# Digital_-_BlackChat.net
KiCad netlist of a schematic drawn in Altium Designer
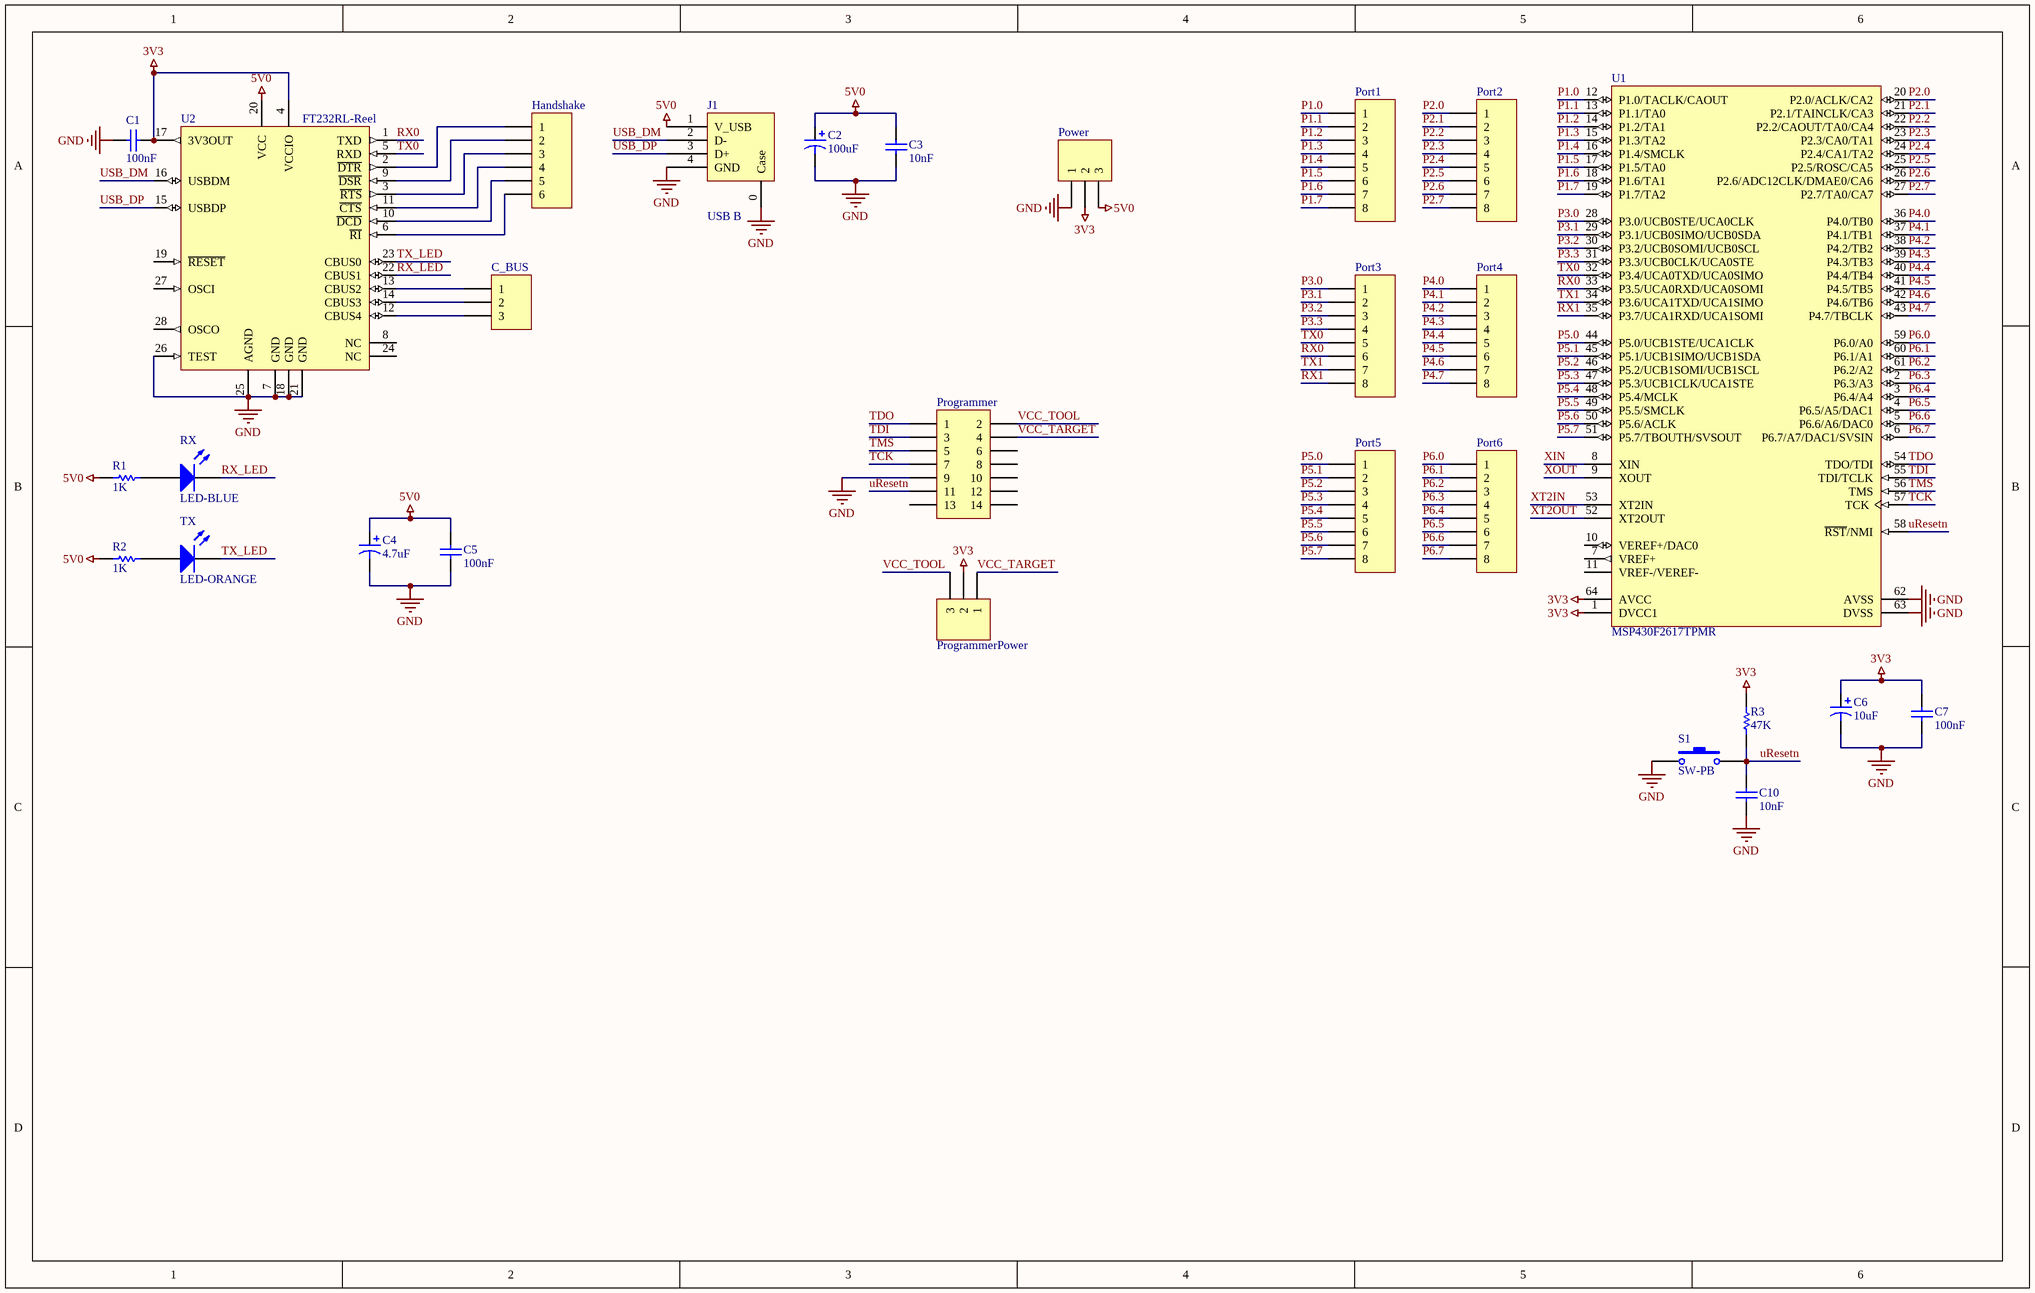
[diagram p0: Digital - BlackChat.SchDoc]

(export (version "E")
  (design (tool "Eeschema 10.0.6"))
  (components
    (comp (ref "C1")
      (value "100nF")
      (footprint "CAP-0805")
      (description "Capacitor")
      (fields (field (name "Comment") "Cap") (field (name "PUBLISHER") "Altium Limited"))
      (libsource (lib "Miscellaneous Devices") (part "Cap"))
    )
    (comp (ref "C2")
      (value "100uF")
      (footprint "CAP-0805")
      (description "Polarized Capacitor (Surface Mount)")
      (fields (field (name "Comment") "Cap Pol3") (field (name "PUBLISHER") "Altium Limited"))
      (libsource (lib "Miscellaneous Devices") (part "Cap Pol3"))
    )
    (comp (ref "C3")
      (value "10nF")
      (footprint "CAP-0805")
      (description "Capacitor")
      (fields (field (name "Comment") "Cap") (field (name "PUBLISHER") "Altium Limited"))
      (libsource (lib "Miscellaneous Devices") (part "Cap"))
    )
    (comp (ref "C4")
      (value "4.7uF")
      (footprint "CAP-0805")
      (description "Polarized Capacitor (Surface Mount)")
      (fields (field (name "Comment") "Cap Pol3") (field (name "PUBLISHER") "Altium Limited"))
      (libsource (lib "Miscellaneous Devices") (part "Cap Pol3"))
    )
    (comp (ref "C5")
      (value "100nF")
      (footprint "CAP-0805")
      (description "Capacitor")
      (fields (field (name "Comment") "Cap") (field (name "PUBLISHER") "Altium Limited"))
      (libsource (lib "Miscellaneous Devices") (part "Cap"))
    )
    (comp (ref "C6")
      (value "10uF")
      (footprint "CAP-0805")
      (description "Polarized Capacitor (Surface Mount)")
      (fields (field (name "Comment") "Cap Pol3") (field (name "PUBLISHER") "Altium Limited"))
      (libsource (lib "Miscellaneous Devices") (part "Cap Pol3"))
    )
    (comp (ref "C7")
      (value "100nF")
      (footprint "CAP-0805")
      (description "Capacitor")
      (fields (field (name "Comment") "Cap") (field (name "PUBLISHER") "Altium Limited"))
      (libsource (lib "Miscellaneous Devices") (part "Cap"))
    )
    (comp (ref "C10")
      (value "10nF")
      (footprint "CAP-0805")
      (description "Capacitor")
      (fields (field (name "Comment") "Cap") (field (name "PUBLISHER") "Altium Limited"))
      (libsource (lib "Miscellaneous Devices") (part "Cap"))
    )
    (comp (ref "C_BUS")
      (value "Header 3")
      (footprint "HDR1X3")
      (description "Header, 3-Pin")
      (fields (field (name "PUBLISHER") "Altium Limited"))
      (libsource (lib "") (part "Header 3_1"))
    )
    (comp (ref "Handshake")
      (value "Header 6")
      (footprint "HDR1X6")
      (description "Header, 6-Pin")
      (fields (field (name "PUBLISHER") "Altium Limited"))
      (libsource (lib "Miscellaneous Connectors") (part "Header 6"))
    )
    (comp (ref "J1")
      (value "USB B")
      (footprint "USB-B")
      (description "On Shore Technology USB-B1HSB6")
      (libsource (lib "BlackChat Library") (part "USB B"))
    )
    (comp (ref "Port1")
      (value "~")
      (footprint "HDR1X8")
      (description "Header, 8-Pin")
      (fields (field (name "PUBLISHER") "Altium Limited"))
      (libsource (lib "Miscellaneous Connectors") (part "Header 8"))
    )
    (comp (ref "Port2")
      (value "~")
      (footprint "HDR1X8")
      (description "Header, 8-Pin")
      (fields (field (name "PUBLISHER") "Altium Limited"))
      (libsource (lib "Miscellaneous Connectors") (part "Header 8"))
    )
    (comp (ref "Port3")
      (value "Header 8")
      (footprint "HDR1X8")
      (description "Header, 8-Pin")
      (fields (field (name "PUBLISHER") "Altium Limited"))
      (libsource (lib "Miscellaneous Connectors") (part "Header 8"))
    )
    (comp (ref "Port4")
      (value "Header 8")
      (footprint "HDR1X8")
      (description "Header, 8-Pin")
      (fields (field (name "PUBLISHER") "Altium Limited"))
      (libsource (lib "Miscellaneous Connectors") (part "Header 8"))
    )
    (comp (ref "Port5")
      (value "Header 8")
      (footprint "HDR1X8")
      (description "Header, 8-Pin")
      (fields (field (name "PUBLISHER") "Altium Limited"))
      (libsource (lib "Miscellaneous Connectors") (part "Header 8"))
    )
    (comp (ref "Port6")
      (value "Header 8")
      (footprint "HDR1X8")
      (description "Header, 8-Pin")
      (fields (field (name "PUBLISHER") "Altium Limited"))
      (libsource (lib "Miscellaneous Connectors") (part "Header 8"))
    )
    (comp (ref "Power")
      (value "Header 3")
      (footprint "HDR1X3")
      (description "Header, 3-Pin")
      (fields (field (name "PUBLISHER") "Altium Limited"))
      (libsource (lib "") (part "Header 3_2"))
    )
    (comp (ref "Programmer")
      (value "Header 7X2")
      (footprint "HDR2X7")
      (description "Header, 7-Pin, Dual row")
      (fields (field (name "PUBLISHER") "Altium Limited"))
      (libsource (lib "Miscellaneous Connectors") (part "Header 7X2"))
    )
    (comp (ref "ProgrammerPower")
      (value "Header 3")
      (footprint "HDR1X3")
      (description "Header, 3-Pin")
      (fields (field (name "PUBLISHER") "Altium Limited"))
      (libsource (lib "Miscellaneous Connectors") (part "Header 3"))
    )
    (comp (ref "R1")
      (value "1K")
      (footprint "RES-0805")
      (description "Resistor")
      (fields (field (name "Comment") "Res1") (field (name "PUBLISHER") "Altium Limited"))
      (libsource (lib "Miscellaneous Devices") (part "Res1"))
    )
    (comp (ref "R2")
      (value "1K")
      (footprint "RES-0805")
      (description "Resistor")
      (fields (field (name "Comment") "Res1") (field (name "PUBLISHER") "Altium Limited"))
      (libsource (lib "Miscellaneous Devices") (part "Res1"))
    )
    (comp (ref "R3")
      (value "47K")
      (footprint "RES-0805")
      (description "Resistor")
      (fields (field (name "Comment") "Res1") (field (name "PUBLISHER") "Altium Limited"))
      (libsource (lib "Miscellaneous Devices") (part "Res1"))
    )
    (comp (ref "RX")
      (value "LED-BLUE")
      (footprint "LED-0805")
      (description "Light Emitting Diode")
      (libsource (lib "BlackChat Library") (part "LED-GENERIC"))
    )
    (comp (ref "S1")
      (value "SW-PB")
      (footprint "SW PB")
      (description "DIGIKEY SW400-ND")
      (fields (field (name "PUBLISHER") "Altium Limited"))
      (libsource (lib "ECE Lib") (part "SW-PB"))
    )
    (comp (ref "TX")
      (value "LED-ORANGE")
      (footprint "LED-0805")
      (description "Light Emitting Diode")
      (libsource (lib "BlackChat Library") (part "LED-GENERIC"))
    )
    (comp (ref "U1")
      (value "MSP430F2617TPMR")
      (footprint "TI-PM64_N")
      (fields (field (name "MANUFACTURER") "Texas Instruments"))
      (libsource (lib "TI Microcontroller MSP430 16-bit Ultra-Low Power") (part "MSP430F2617TPMR"))
    )
    (comp (ref "U2")
      (value "FT232RL-Reel")
      (footprint "SSOP-28_N")
      (description "USB UART Asynchronous Serial Data Transfer Chip, SSOP-28, Tape and Reel")
      (fields (field (name "PUBLISHER") "Altium Limited"))
      (libsource (lib "BlackChat Library") (part "FT232RL-Reel"))
    )
  )
  (nets
    (net (code "1") (name "/P1.0") (class "Default")
      (node (ref "Port1") (pin "1") (pinfunction "1_1") (pintype "passive"))
      (node (ref "U1") (pin "12") (pinfunction "P1.0/TACLK/CAOUT_12") (pintype "bidirectional"))
    )
    (net (code "2") (name "/P1.1") (class "Default")
      (node (ref "Port1") (pin "2") (pinfunction "2_2") (pintype "passive"))
      (node (ref "U1") (pin "13") (pinfunction "P1.1/TA0_13") (pintype "bidirectional"))
    )
    (net (code "3") (name "/P1.2") (class "Default")
      (node (ref "Port1") (pin "3") (pinfunction "3_3") (pintype "passive"))
      (node (ref "U1") (pin "14") (pinfunction "P1.2/TA1_14") (pintype "bidirectional"))
    )
    (net (code "4") (name "/P1.3") (class "Default")
      (node (ref "Port1") (pin "4") (pinfunction "4_4") (pintype "passive"))
      (node (ref "U1") (pin "15") (pinfunction "P1.3/TA2_15") (pintype "bidirectional"))
    )
    (net (code "5") (name "/P1.4") (class "Default")
      (node (ref "Port1") (pin "5") (pinfunction "5_5") (pintype "passive"))
      (node (ref "U1") (pin "16") (pinfunction "P1.4/SMCLK_16") (pintype "bidirectional"))
    )
    (net (code "6") (name "/P1.5") (class "Default")
      (node (ref "Port1") (pin "6") (pinfunction "6_6") (pintype "passive"))
      (node (ref "U1") (pin "17") (pinfunction "P1.5/TA0_17") (pintype "bidirectional"))
    )
    (net (code "7") (name "/P1.6") (class "Default")
      (node (ref "Port1") (pin "7") (pinfunction "7_7") (pintype "passive"))
      (node (ref "U1") (pin "18") (pinfunction "P1.6/TA1_18") (pintype "bidirectional"))
    )
    (net (code "8") (name "/P1.7") (class "Default")
      (node (ref "Port1") (pin "8") (pinfunction "8_8") (pintype "passive"))
      (node (ref "U1") (pin "19") (pinfunction "P1.7/TA2_19") (pintype "bidirectional"))
    )
    (net (code "9") (name "/P2.0") (class "Default")
      (node (ref "Port2") (pin "1") (pinfunction "1_1") (pintype "passive"))
      (node (ref "U1") (pin "20") (pinfunction "P2.0/ACLK/CA2_20") (pintype "bidirectional"))
    )
    (net (code "10") (name "/P2.1") (class "Default")
      (node (ref "Port2") (pin "2") (pinfunction "2_2") (pintype "passive"))
      (node (ref "U1") (pin "21") (pinfunction "P2.1/TAINCLK/CA3_21") (pintype "bidirectional"))
    )
    (net (code "11") (name "/P2.2") (class "Default")
      (node (ref "Port2") (pin "3") (pinfunction "3_3") (pintype "passive"))
      (node (ref "U1") (pin "22") (pinfunction "P2.2/CAOUT/TA0/CA4_22") (pintype "bidirectional"))
    )
    (net (code "12") (name "/P2.3") (class "Default")
      (node (ref "Port2") (pin "4") (pinfunction "4_4") (pintype "passive"))
      (node (ref "U1") (pin "23") (pinfunction "P2.3/CA0/TA1_23") (pintype "bidirectional"))
    )
    (net (code "13") (name "/P2.4") (class "Default")
      (node (ref "Port2") (pin "5") (pinfunction "5_5") (pintype "passive"))
      (node (ref "U1") (pin "24") (pinfunction "P2.4/CA1/TA2_24") (pintype "bidirectional"))
    )
    (net (code "14") (name "/P2.5") (class "Default")
      (node (ref "Port2") (pin "6") (pinfunction "6_6") (pintype "passive"))
      (node (ref "U1") (pin "25") (pinfunction "P2.5/ROSC/CA5_25") (pintype "bidirectional"))
    )
    (net (code "15") (name "/P2.6") (class "Default")
      (node (ref "Port2") (pin "7") (pinfunction "7_7") (pintype "passive"))
      (node (ref "U1") (pin "26") (pinfunction "P2.6/ADC12CLK/DMAE0/CA6_26") (pintype "bidirectional"))
    )
    (net (code "16") (name "/P2.7") (class "Default")
      (node (ref "Port2") (pin "8") (pinfunction "8_8") (pintype "passive"))
      (node (ref "U1") (pin "27") (pinfunction "P2.7/TA0/CA7_27") (pintype "bidirectional"))
    )
    (net (code "17") (name "/P3.0") (class "Default")
      (node (ref "Port3") (pin "1") (pinfunction "1_1") (pintype "passive"))
      (node (ref "U1") (pin "28") (pinfunction "P3.0/UCB0STE/UCA0CLK_28") (pintype "bidirectional"))
    )
    (net (code "18") (name "/P3.1") (class "Default")
      (node (ref "Port3") (pin "2") (pinfunction "2_2") (pintype "passive"))
      (node (ref "U1") (pin "29") (pinfunction "P3.1/UCB0SIMO/UCB0SDA_29") (pintype "bidirectional"))
    )
    (net (code "19") (name "/P3.2") (class "Default")
      (node (ref "Port3") (pin "3") (pinfunction "3_3") (pintype "passive"))
      (node (ref "U1") (pin "30") (pinfunction "P3.2/UCB0SOMI/UCB0SCL_30") (pintype "bidirectional"))
    )
    (net (code "20") (name "/P3.3") (class "Default")
      (node (ref "Port3") (pin "4") (pinfunction "4_4") (pintype "passive"))
      (node (ref "U1") (pin "31") (pinfunction "P3.3/UCB0CLK/UCA0STE_31") (pintype "bidirectional"))
    )
    (net (code "21") (name "/P4.0") (class "Default")
      (node (ref "Port4") (pin "1") (pinfunction "1_1") (pintype "passive"))
      (node (ref "U1") (pin "36") (pinfunction "P4.0/TB0_36") (pintype "bidirectional"))
    )
    (net (code "22") (name "/P4.1") (class "Default")
      (node (ref "Port4") (pin "2") (pinfunction "2_2") (pintype "passive"))
      (node (ref "U1") (pin "37") (pinfunction "P4.1/TB1_37") (pintype "bidirectional"))
    )
    (net (code "23") (name "/P4.2") (class "Default")
      (node (ref "Port4") (pin "3") (pinfunction "3_3") (pintype "passive"))
      (node (ref "U1") (pin "38") (pinfunction "P4.2/TB2_38") (pintype "bidirectional"))
    )
    (net (code "24") (name "/P4.3") (class "Default")
      (node (ref "Port4") (pin "4") (pinfunction "4_4") (pintype "passive"))
      (node (ref "U1") (pin "39") (pinfunction "P4.3/TB3_39") (pintype "bidirectional"))
    )
    (net (code "25") (name "/P4.4") (class "Default")
      (node (ref "Port4") (pin "5") (pinfunction "5_5") (pintype "passive"))
      (node (ref "U1") (pin "40") (pinfunction "P4.4/TB4_40") (pintype "bidirectional"))
    )
    (net (code "26") (name "/P4.5") (class "Default")
      (node (ref "Port4") (pin "6") (pinfunction "6_6") (pintype "passive"))
      (node (ref "U1") (pin "41") (pinfunction "P4.5/TB5_41") (pintype "bidirectional"))
    )
    (net (code "27") (name "/P4.6") (class "Default")
      (node (ref "Port4") (pin "7") (pinfunction "7_7") (pintype "passive"))
      (node (ref "U1") (pin "42") (pinfunction "P4.6/TB6_42") (pintype "bidirectional"))
    )
    (net (code "28") (name "/P4.7") (class "Default")
      (node (ref "Port4") (pin "8") (pinfunction "8_8") (pintype "passive"))
      (node (ref "U1") (pin "43") (pinfunction "P4.7/TBCLK_43") (pintype "bidirectional"))
    )
    (net (code "29") (name "/P5.0") (class "Default")
      (node (ref "Port5") (pin "1") (pinfunction "1_1") (pintype "passive"))
      (node (ref "U1") (pin "44") (pinfunction "P5.0/UCB1STE/UCA1CLK_44") (pintype "bidirectional"))
    )
    (net (code "30") (name "/P5.1") (class "Default")
      (node (ref "Port5") (pin "2") (pinfunction "2_2") (pintype "passive"))
      (node (ref "U1") (pin "45") (pinfunction "P5.1/UCB1SIMO/UCB1SDA_45") (pintype "bidirectional"))
    )
    (net (code "31") (name "/P5.2") (class "Default")
      (node (ref "Port5") (pin "3") (pinfunction "3_3") (pintype "passive"))
      (node (ref "U1") (pin "46") (pinfunction "P5.2/UCB1SOMI/UCB1SCL_46") (pintype "bidirectional"))
    )
    (net (code "32") (name "/P5.3") (class "Default")
      (node (ref "Port5") (pin "4") (pinfunction "4_4") (pintype "passive"))
      (node (ref "U1") (pin "47") (pinfunction "P5.3/UCB1CLK/UCA1STE_47") (pintype "bidirectional"))
    )
    (net (code "33") (name "/P5.4") (class "Default")
      (node (ref "Port5") (pin "5") (pinfunction "5_5") (pintype "passive"))
      (node (ref "U1") (pin "48") (pinfunction "P5.4/MCLK_48") (pintype "bidirectional"))
    )
    (net (code "34") (name "/P5.5") (class "Default")
      (node (ref "Port5") (pin "6") (pinfunction "6_6") (pintype "passive"))
      (node (ref "U1") (pin "49") (pinfunction "P5.5/SMCLK_49") (pintype "bidirectional"))
    )
    (net (code "35") (name "/P5.6") (class "Default")
      (node (ref "Port5") (pin "7") (pinfunction "7_7") (pintype "passive"))
      (node (ref "U1") (pin "50") (pinfunction "P5.6/ACLK_50") (pintype "bidirectional"))
    )
    (net (code "36") (name "/P5.7") (class "Default")
      (node (ref "Port5") (pin "8") (pinfunction "8_8") (pintype "passive"))
      (node (ref "U1") (pin "51") (pinfunction "P5.7/TBOUTH/SVSOUT_51") (pintype "bidirectional"))
    )
    (net (code "37") (name "/P6.0") (class "Default")
      (node (ref "Port6") (pin "1") (pinfunction "1_1") (pintype "passive"))
      (node (ref "U1") (pin "59") (pinfunction "P6.0/A0_59") (pintype "bidirectional"))
    )
    (net (code "38") (name "/P6.1") (class "Default")
      (node (ref "Port6") (pin "2") (pinfunction "2_2") (pintype "passive"))
      (node (ref "U1") (pin "60") (pinfunction "P6.1/A1_60") (pintype "bidirectional"))
    )
    (net (code "39") (name "/P6.2") (class "Default")
      (node (ref "Port6") (pin "3") (pinfunction "3_3") (pintype "passive"))
      (node (ref "U1") (pin "61") (pinfunction "P6.2/A2_61") (pintype "bidirectional"))
    )
    (net (code "40") (name "/P6.3") (class "Default")
      (node (ref "Port6") (pin "4") (pinfunction "4_4") (pintype "passive"))
      (node (ref "U1") (pin "2") (pinfunction "P6.3/A3_2") (pintype "bidirectional"))
    )
    (net (code "41") (name "/P6.4") (class "Default")
      (node (ref "Port6") (pin "5") (pinfunction "5_5") (pintype "passive"))
      (node (ref "U1") (pin "3") (pinfunction "P6.4/A4_3") (pintype "bidirectional"))
    )
    (net (code "42") (name "/P6.5") (class "Default")
      (node (ref "Port6") (pin "6") (pinfunction "6_6") (pintype "passive"))
      (node (ref "U1") (pin "4") (pinfunction "P6.5/A5/DAC1_4") (pintype "bidirectional"))
    )
    (net (code "43") (name "/P6.6") (class "Default")
      (node (ref "Port6") (pin "7") (pinfunction "7_7") (pintype "passive"))
      (node (ref "U1") (pin "5") (pinfunction "P6.6/A6/DAC0_5") (pintype "bidirectional"))
    )
    (net (code "44") (name "/P6.7") (class "Default")
      (node (ref "Port6") (pin "8") (pinfunction "8_8") (pintype "passive"))
      (node (ref "U1") (pin "6") (pinfunction "P6.7/A7/DAC1/SVSIN_6") (pintype "bidirectional"))
    )
    (net (code "45") (name "/RX0") (class "Default")
      (node (ref "Port3") (pin "6") (pinfunction "6_6") (pintype "passive"))
      (node (ref "U1") (pin "33") (pinfunction "P3.5/UCA0RXD/UCA0SOMI_33") (pintype "bidirectional"))
      (node (ref "U2") (pin "1") (pinfunction "TXD_1") (pintype "output"))
    )
    (net (code "46") (name "/RX1") (class "Default")
      (node (ref "Port3") (pin "8") (pinfunction "8_8") (pintype "passive"))
      (node (ref "U1") (pin "35") (pinfunction "P3.7/UCA1RXD/UCA1SOMI_35") (pintype "bidirectional"))
    )
    (net (code "47") (name "/RX_LED") (class "Default")
      (node (ref "RX") (pin "2") (pinfunction "K_2") (pintype "passive"))
      (node (ref "U2") (pin "22") (pinfunction "CBUS1_22") (pintype "bidirectional"))
    )
    (net (code "48") (name "/TCK") (class "Default")
      (node (ref "Programmer") (pin "7") (pinfunction "7_7") (pintype "passive"))
      (node (ref "U1") (pin "57") (pinfunction "TCK_57") (pintype "input"))
    )
    (net (code "49") (name "/TDI") (class "Default")
      (node (ref "Programmer") (pin "3") (pinfunction "3_3") (pintype "passive"))
      (node (ref "U1") (pin "55") (pinfunction "TDI/TCLK_55") (pintype "input"))
    )
    (net (code "50") (name "/TDO") (class "Default")
      (node (ref "Programmer") (pin "1") (pinfunction "1_1") (pintype "passive"))
      (node (ref "U1") (pin "54") (pinfunction "TDO/TDI_54") (pintype "bidirectional"))
    )
    (net (code "51") (name "/TMS") (class "Default")
      (node (ref "Programmer") (pin "5") (pinfunction "5_5") (pintype "passive"))
      (node (ref "U1") (pin "56") (pinfunction "TMS_56") (pintype "input"))
    )
    (net (code "52") (name "/TX0") (class "Default")
      (node (ref "Port3") (pin "5") (pinfunction "5_5") (pintype "passive"))
      (node (ref "U1") (pin "32") (pinfunction "P3.4/UCA0TXD/UCA0SIMO_32") (pintype "bidirectional"))
      (node (ref "U2") (pin "5") (pinfunction "RXD_5") (pintype "input"))
    )
    (net (code "53") (name "/TX1") (class "Default")
      (node (ref "Port3") (pin "7") (pinfunction "7_7") (pintype "passive"))
      (node (ref "U1") (pin "34") (pinfunction "P3.6/UCA1TXD/UCA1SIMO_34") (pintype "bidirectional"))
    )
    (net (code "54") (name "/TX_LED") (class "Default")
      (node (ref "TX") (pin "2") (pinfunction "K_2") (pintype "passive"))
      (node (ref "U2") (pin "23") (pinfunction "CBUS0_23") (pintype "bidirectional"))
    )
    (net (code "55") (name "/USB_DM") (class "Default")
      (node (ref "J1") (pin "2") (pinfunction "D-_2") (pintype "passive"))
      (node (ref "U2") (pin "16") (pinfunction "USBDM_16") (pintype "bidirectional"))
    )
    (net (code "56") (name "/USB_DP") (class "Default")
      (node (ref "J1") (pin "3") (pinfunction "D+_3") (pintype "passive"))
      (node (ref "U2") (pin "15") (pinfunction "USBDP_15") (pintype "bidirectional"))
    )
    (net (code "57") (name "/VCC_TARGET") (class "Default")
      (node (ref "Programmer") (pin "4") (pinfunction "4_4") (pintype "passive"))
      (node (ref "ProgrammerPower") (pin "1") (pinfunction "1_1") (pintype "passive"))
    )
    (net (code "58") (name "/VCC_TOOL") (class "Default")
      (node (ref "Programmer") (pin "2") (pinfunction "2_2") (pintype "passive"))
      (node (ref "ProgrammerPower") (pin "3") (pinfunction "3_3") (pintype "passive"))
    )
    (net (code "59") (name "/XIN") (class "Default")
      (node (ref "U1") (pin "8") (pinfunction "XIN_8") (pintype "passive"))
    )
    (net (code "60") (name "/XOUT") (class "Default")
      (node (ref "U1") (pin "9") (pinfunction "XOUT_9") (pintype "passive"))
    )
    (net (code "61") (name "/XT2IN") (class "Default")
      (node (ref "U1") (pin "53") (pinfunction "XT2IN_53") (pintype "passive"))
    )
    (net (code "62") (name "/XT2OUT") (class "Default")
      (node (ref "U1") (pin "52") (pinfunction "XT2OUT_52") (pintype "passive"))
    )
    (net (code "63") (name "/uResetn") (class "Default")
      (node (ref "C10") (pin "2") (pinfunction "2_2") (pintype "passive"))
      (node (ref "Programmer") (pin "11") (pinfunction "11_11") (pintype "passive"))
      (node (ref "R3") (pin "1") (pinfunction "1_1") (pintype "passive"))
      (node (ref "S1") (pin "2") (pinfunction "2_2") (pintype "passive"))
      (node (ref "U1") (pin "58") (pinfunction "~{RST}/NMI_58") (pintype "input"))
    )
    (net (code "64") (name "3V3") (class "Default")
      (node (ref "C1") (pin "1") (pinfunction "1_1") (pintype "passive"))
      (node (ref "C6") (pin "1") (pinfunction "1_1") (pintype "passive"))
      (node (ref "C7") (pin "2") (pinfunction "2_2") (pintype "passive"))
      (node (ref "Power") (pin "2") (pinfunction "2_2") (pintype "passive"))
      (node (ref "ProgrammerPower") (pin "2") (pinfunction "2_2") (pintype "passive"))
      (node (ref "R3") (pin "2") (pinfunction "2_2") (pintype "passive"))
      (node (ref "U1") (pin "1") (pinfunction "DVCC1_1") (pintype "power_in"))
      (node (ref "U1") (pin "64") (pinfunction "AVCC_64") (pintype "power_in"))
      (node (ref "U2") (pin "17") (pinfunction "3V3OUT_17") (pintype "output"))
      (node (ref "U2") (pin "4") (pinfunction "VCCIO_4") (pintype "power_in"))
    )
    (net (code "65") (name "5V0") (class "Default")
      (node (ref "C2") (pin "1") (pinfunction "1_1") (pintype "passive"))
      (node (ref "C3") (pin "2") (pinfunction "2_2") (pintype "passive"))
      (node (ref "C4") (pin "1") (pinfunction "1_1") (pintype "passive"))
      (node (ref "C5") (pin "2") (pinfunction "2_2") (pintype "passive"))
      (node (ref "J1") (pin "1") (pinfunction "V_USB_1") (pintype "passive"))
      (node (ref "Power") (pin "3") (pinfunction "3_3") (pintype "passive"))
      (node (ref "R1") (pin "2") (pinfunction "2_2") (pintype "passive"))
      (node (ref "R2") (pin "2") (pinfunction "2_2") (pintype "passive"))
      (node (ref "U2") (pin "20") (pinfunction "VCC_20") (pintype "power_in"))
    )
    (net (code "66") (name "GND") (class "Default")
      (node (ref "C1") (pin "2") (pinfunction "2_2") (pintype "passive"))
      (node (ref "C10") (pin "1") (pinfunction "1_1") (pintype "passive"))
      (node (ref "C2") (pin "2") (pinfunction "2_2") (pintype "passive"))
      (node (ref "C3") (pin "1") (pinfunction "1_1") (pintype "passive"))
      (node (ref "C4") (pin "2") (pinfunction "2_2") (pintype "passive"))
      (node (ref "C5") (pin "1") (pinfunction "1_1") (pintype "passive"))
      (node (ref "C6") (pin "2") (pinfunction "2_2") (pintype "passive"))
      (node (ref "C7") (pin "1") (pinfunction "1_1") (pintype "passive"))
      (node (ref "J1") (pin "0") (pinfunction "Case_0") (pintype "passive"))
      (node (ref "J1") (pin "4") (pinfunction "GND_4") (pintype "passive"))
      (node (ref "Power") (pin "1") (pinfunction "1_1") (pintype "passive"))
      (node (ref "Programmer") (pin "9") (pinfunction "9_9") (pintype "passive"))
      (node (ref "S1") (pin "1") (pinfunction "1_1") (pintype "passive"))
      (node (ref "U1") (pin "62") (pinfunction "AVSS_62") (pintype "power_in"))
      (node (ref "U1") (pin "63") (pinfunction "DVSS_63") (pintype "power_in"))
      (node (ref "U2") (pin "18") (pinfunction "GND_18") (pintype "power_in"))
      (node (ref "U2") (pin "21") (pinfunction "GND_21") (pintype "power_in"))
      (node (ref "U2") (pin "25") (pinfunction "AGND_25") (pintype "power_in"))
      (node (ref "U2") (pin "26") (pinfunction "TEST_26") (pintype "input"))
      (node (ref "U2") (pin "7") (pinfunction "GND_7") (pintype "power_in"))
    )
    (net (code "67") (name "Net-(RX-A)") (class "Default")
      (node (ref "R1") (pin "1") (pinfunction "1_1") (pintype "passive"))
      (node (ref "RX") (pin "1") (pinfunction "A_1") (pintype "passive"))
    )
    (net (code "68") (name "Net-(TX-A)") (class "Default")
      (node (ref "R2") (pin "1") (pinfunction "1_1") (pintype "passive"))
      (node (ref "TX") (pin "1") (pinfunction "A_1") (pintype "passive"))
    )
    (net (code "69") (name "Net-(U2-CBUS2)") (class "Default")
      (node (ref "C_BUS") (pin "1") (pinfunction "1_1") (pintype "passive"))
      (node (ref "U2") (pin "13") (pinfunction "CBUS2_13") (pintype "bidirectional"))
    )
    (net (code "70") (name "Net-(U2-CBUS3)") (class "Default")
      (node (ref "C_BUS") (pin "2") (pinfunction "2_2") (pintype "passive"))
      (node (ref "U2") (pin "14") (pinfunction "CBUS3_14") (pintype "bidirectional"))
    )
    (net (code "71") (name "Net-(U2-CBUS4)") (class "Default")
      (node (ref "C_BUS") (pin "3") (pinfunction "3_3") (pintype "passive"))
      (node (ref "U2") (pin "12") (pinfunction "CBUS4_12") (pintype "bidirectional"))
    )
    (net (code "72") (name "Net-(U2-~{CTS})") (class "Default")
      (node (ref "Handshake") (pin "4") (pinfunction "4_4") (pintype "passive"))
      (node (ref "U2") (pin "11") (pinfunction "~{CTS}_11") (pintype "input"))
    )
    (net (code "73") (name "Net-(U2-~{DCD})") (class "Default")
      (node (ref "Handshake") (pin "5") (pinfunction "5_5") (pintype "passive"))
      (node (ref "U2") (pin "10") (pinfunction "~{DCD}_10") (pintype "input"))
    )
    (net (code "74") (name "Net-(U2-~{DSR})") (class "Default")
      (node (ref "Handshake") (pin "2") (pinfunction "2_2") (pintype "passive"))
      (node (ref "U2") (pin "9") (pinfunction "~{DSR}_9") (pintype "input"))
    )
    (net (code "75") (name "Net-(U2-~{DTR})") (class "Default")
      (node (ref "Handshake") (pin "1") (pinfunction "1_1") (pintype "passive"))
      (node (ref "U2") (pin "2") (pinfunction "~{DTR}_2") (pintype "output"))
    )
    (net (code "76") (name "Net-(U2-~{RI})") (class "Default")
      (node (ref "Handshake") (pin "6") (pinfunction "6_6") (pintype "passive"))
      (node (ref "U2") (pin "6") (pinfunction "~{RI}_6") (pintype "input"))
    )
    (net (code "77") (name "Net-(U2-~{RTS})") (class "Default")
      (node (ref "Handshake") (pin "3") (pinfunction "3_3") (pintype "passive"))
      (node (ref "U2") (pin "3") (pinfunction "~{RTS}_3") (pintype "output"))
    )
    (net (code "78") (name "unconnected-(Programmer-Pad6)") (class "Default")
      (node (ref "Programmer") (pin "6") (pinfunction "6_6") (pintype "passive"))
    )
    (net (code "79") (name "unconnected-(Programmer-Pad8)") (class "Default")
      (node (ref "Programmer") (pin "8") (pinfunction "8_8") (pintype "passive"))
    )
    (net (code "80") (name "unconnected-(Programmer-Pad10)") (class "Default")
      (node (ref "Programmer") (pin "10") (pinfunction "10_10") (pintype "passive"))
    )
    (net (code "81") (name "unconnected-(Programmer-Pad12)") (class "Default")
      (node (ref "Programmer") (pin "12") (pinfunction "12_12") (pintype "passive"))
    )
    (net (code "82") (name "unconnected-(Programmer-Pad13)") (class "Default")
      (node (ref "Programmer") (pin "13") (pinfunction "13_13") (pintype "passive"))
    )
    (net (code "83") (name "unconnected-(Programmer-Pad14)") (class "Default")
      (node (ref "Programmer") (pin "14") (pinfunction "14_14") (pintype "passive"))
    )
    (net (code "84") (name "unconnected-(U1-VEREF+{slash}DAC0-Pad10)") (class "Default")
      (node (ref "U1") (pin "10") (pinfunction "VEREF+/DAC0_10") (pintype "bidirectional"))
    )
    (net (code "85") (name "unconnected-(U1-VREF+-Pad7)") (class "Default")
      (node (ref "U1") (pin "7") (pinfunction "VREF+_7") (pintype "output"))
    )
    (net (code "86") (name "unconnected-(U1-VREF-{slash}VEREF--Pad11)") (class "Default")
      (node (ref "U1") (pin "11") (pinfunction "VREF-/VEREF-_11") (pintype "passive"))
    )
    (net (code "87") (name "unconnected-(U2-NC-Pad8)") (class "Default")
      (node (ref "U2") (pin "8") (pinfunction "NC_8") (pintype "passive"))
    )
    (net (code "88") (name "unconnected-(U2-NC-Pad24)") (class "Default")
      (node (ref "U2") (pin "24") (pinfunction "NC_24") (pintype "passive"))
    )
    (net (code "89") (name "unconnected-(U2-OSCI-Pad27)") (class "Default")
      (node (ref "U2") (pin "27") (pinfunction "OSCI_27") (pintype "input"))
    )
    (net (code "90") (name "unconnected-(U2-OSCO-Pad28)") (class "Default")
      (node (ref "U2") (pin "28") (pinfunction "OSCO_28") (pintype "output"))
    )
    (net (code "91") (name "unconnected-(U2-~{RESET}-Pad19)") (class "Default")
      (node (ref "U2") (pin "19") (pinfunction "~{RESET}_19") (pintype "input"))
    )
  )
)
